# Battery_Monitor.net
KiCad netlist of a schematic drawn in EAGLE
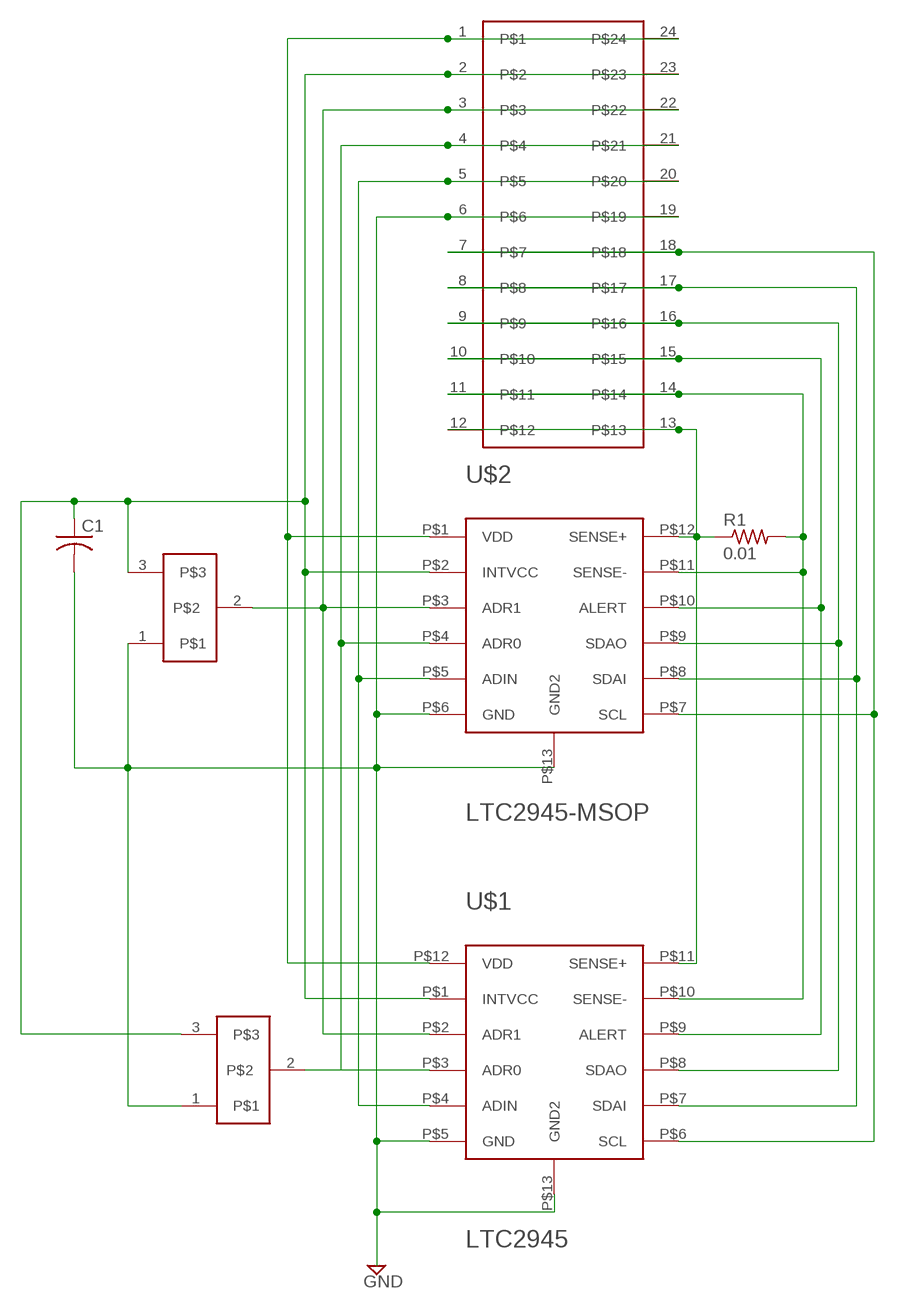
[diagram p0: schematic, sheet 1]

(export (version "E")
  (design (tool "Eeschema 10.0.6"))
  (components
    (comp (ref "C1")
      (value "C-USC1812")
      (footprint "eagle-import:C1812")
      (libsource (lib "eagle-import") (part "C-USC1812"))
    )
    (comp (ref "R1")
      (value "0.01")
      (footprint "eagle-import:R2010")
      (libsource (lib "eagle-import") (part "R-US_R2010"))
    )
    (comp (ref "U$1")
      (value "LTC2945")
      (footprint "eagle-import:QFN12")
      (libsource (lib "eagle-import") (part "LTC2945"))
    )
    (comp (ref "U$2")
      (value "LTC2945-MSOP")
      (footprint "eagle-import:MSOP12")
      (libsource (lib "eagle-import") (part "LTC2945-MSOP"))
    )
    (comp (ref "U$3")
      (value "24-PINEVAL")
      (footprint "eagle-import:DIL24-6")
      (libsource (lib "eagle-import") (part "24-PINEVAL"))
    )
    (comp (ref "U$4")
      (value "JUMP-3")
      (footprint "eagle-import:JUMP-3")
      (libsource (lib "eagle-import") (part "JUMP-3"))
    )
    (comp (ref "U$5")
      (value "JUMP-3")
      (footprint "eagle-import:JUMP-3")
      (libsource (lib "eagle-import") (part "JUMP-3"))
    )
  )
  (nets
    (net (code "2") (name "Net-(U$1-ADIN)") (class "Default")
      (node (ref "U$1") (pin "P$4") (pinfunction "ADIN_P$4") (pintype "bidirectional"))
      (node (ref "U$2") (pin "P$5") (pinfunction "ADIN_P$5") (pintype "bidirectional"))
      (node (ref "U$3") (pin "20") (pinfunction "P$20_20") (pintype "bidirectional"))
      (node (ref "U$3") (pin "5") (pinfunction "P$5_5") (pintype "bidirectional"))
    )
    (net (code "3") (name "Net-(U$1-ADR0)") (class "Default")
      (node (ref "U$1") (pin "P$3") (pinfunction "ADR0_P$3") (pintype "bidirectional"))
      (node (ref "U$2") (pin "P$4") (pinfunction "ADR0_P$4") (pintype "bidirectional"))
      (node (ref "U$3") (pin "21") (pinfunction "P$21_21") (pintype "bidirectional"))
      (node (ref "U$3") (pin "4") (pinfunction "P$4_4") (pintype "bidirectional"))
      (node (ref "U$5") (pin "2") (pinfunction "P$2_2") (pintype "bidirectional"))
    )
    (net (code "4") (name "Net-(U$1-ADR1)") (class "Default")
      (node (ref "U$1") (pin "P$2") (pinfunction "ADR1_P$2") (pintype "bidirectional"))
      (node (ref "U$2") (pin "P$3") (pinfunction "ADR1_P$3") (pintype "bidirectional"))
      (node (ref "U$3") (pin "22") (pinfunction "P$22_22") (pintype "bidirectional"))
      (node (ref "U$3") (pin "3") (pinfunction "P$3_3") (pintype "bidirectional"))
      (node (ref "U$4") (pin "2") (pinfunction "P$2_2") (pintype "bidirectional"))
    )
    (net (code "5") (name "Net-(U$1-ALERT)") (class "Default")
      (node (ref "U$1") (pin "P$9") (pinfunction "ALERT_P$9") (pintype "bidirectional"))
      (node (ref "U$2") (pin "P$10") (pinfunction "ALERT_P$10") (pintype "bidirectional"))
      (node (ref "U$3") (pin "10") (pinfunction "P$10_10") (pintype "bidirectional"))
      (node (ref "U$3") (pin "15") (pinfunction "P$15_15") (pintype "bidirectional"))
    )
    (net (code "6") (name "Net-(U$1-GND)") (class "Default")
      (node (ref "C1") (pin "2") (pinfunction "2_2") (pintype "passive"))
      (node (ref "U$1") (pin "P$13") (pinfunction "GND2_P$13") (pintype "bidirectional"))
      (node (ref "U$1") (pin "P$5") (pinfunction "GND_P$5") (pintype "bidirectional"))
      (node (ref "U$2") (pin "P$13") (pinfunction "GND2_P$13") (pintype "bidirectional"))
      (node (ref "U$2") (pin "P$6") (pinfunction "GND_P$6") (pintype "bidirectional"))
      (node (ref "U$3") (pin "19") (pinfunction "P$19_19") (pintype "bidirectional"))
      (node (ref "U$3") (pin "6") (pinfunction "P$6_6") (pintype "bidirectional"))
      (node (ref "U$4") (pin "1") (pinfunction "P$1_1") (pintype "bidirectional"))
      (node (ref "U$5") (pin "1") (pinfunction "P$1_1") (pintype "bidirectional"))
    )
    (net (code "7") (name "Net-(U$1-INTVCC)") (class "Default")
      (node (ref "C1") (pin "1") (pinfunction "1_1") (pintype "passive"))
      (node (ref "U$1") (pin "P$1") (pinfunction "INTVCC_P$1") (pintype "bidirectional"))
      (node (ref "U$2") (pin "P$2") (pinfunction "INTVCC_P$2") (pintype "bidirectional"))
      (node (ref "U$3") (pin "2") (pinfunction "P$2_2") (pintype "bidirectional"))
      (node (ref "U$3") (pin "23") (pinfunction "P$23_23") (pintype "bidirectional"))
      (node (ref "U$4") (pin "3") (pinfunction "P$3_3") (pintype "bidirectional"))
      (node (ref "U$5") (pin "3") (pinfunction "P$3_3") (pintype "bidirectional"))
    )
    (net (code "8") (name "Net-(U$1-SCL)") (class "Default")
      (node (ref "U$1") (pin "P$6") (pinfunction "SCL_P$6") (pintype "bidirectional"))
      (node (ref "U$2") (pin "P$7") (pinfunction "SCL_P$7") (pintype "bidirectional"))
      (node (ref "U$3") (pin "18") (pinfunction "P$18_18") (pintype "bidirectional"))
      (node (ref "U$3") (pin "7") (pinfunction "P$7_7") (pintype "bidirectional"))
    )
    (net (code "9") (name "Net-(U$1-SDAI)") (class "Default")
      (node (ref "U$1") (pin "P$7") (pinfunction "SDAI_P$7") (pintype "bidirectional"))
      (node (ref "U$2") (pin "P$8") (pinfunction "SDAI_P$8") (pintype "bidirectional"))
      (node (ref "U$3") (pin "17") (pinfunction "P$17_17") (pintype "bidirectional"))
      (node (ref "U$3") (pin "8") (pinfunction "P$8_8") (pintype "bidirectional"))
    )
    (net (code "10") (name "Net-(U$1-SDAO)") (class "Default")
      (node (ref "U$1") (pin "P$8") (pinfunction "SDAO_P$8") (pintype "bidirectional"))
      (node (ref "U$2") (pin "P$9") (pinfunction "SDAO_P$9") (pintype "bidirectional"))
      (node (ref "U$3") (pin "16") (pinfunction "P$16_16") (pintype "bidirectional"))
      (node (ref "U$3") (pin "9") (pinfunction "P$9_9") (pintype "bidirectional"))
    )
    (net (code "11") (name "Net-(U$1-SENSE+)") (class "Default")
      (node (ref "R1") (pin "1") (pinfunction "1_1") (pintype "passive"))
      (node (ref "U$1") (pin "P$11") (pinfunction "SENSE+_P$11") (pintype "bidirectional"))
      (node (ref "U$2") (pin "P$12") (pinfunction "SENSE+_P$12") (pintype "bidirectional"))
      (node (ref "U$3") (pin "12") (pinfunction "P$12_12") (pintype "bidirectional"))
      (node (ref "U$3") (pin "13") (pinfunction "P$13_13") (pintype "bidirectional"))
    )
    (net (code "12") (name "Net-(U$1-SENSE-)") (class "Default")
      (node (ref "R1") (pin "2") (pinfunction "2_2") (pintype "passive"))
      (node (ref "U$1") (pin "P$10") (pinfunction "SENSE-_P$10") (pintype "bidirectional"))
      (node (ref "U$2") (pin "P$11") (pinfunction "SENSE-_P$11") (pintype "bidirectional"))
      (node (ref "U$3") (pin "11") (pinfunction "P$11_11") (pintype "bidirectional"))
      (node (ref "U$3") (pin "14") (pinfunction "P$14_14") (pintype "bidirectional"))
    )
    (net (code "13") (name "Net-(U$1-VDD)") (class "Default")
      (node (ref "U$1") (pin "P$12") (pinfunction "VDD_P$12") (pintype "bidirectional"))
      (node (ref "U$2") (pin "P$1") (pinfunction "VDD_P$1") (pintype "bidirectional"))
      (node (ref "U$3") (pin "1") (pinfunction "P$1_1") (pintype "bidirectional"))
      (node (ref "U$3") (pin "24") (pinfunction "P$24_24") (pintype "bidirectional"))
    )
  )
)
